# PCB_RGBlimp-Q.net
KiCad netlist of a schematic drawn in Altium Designer
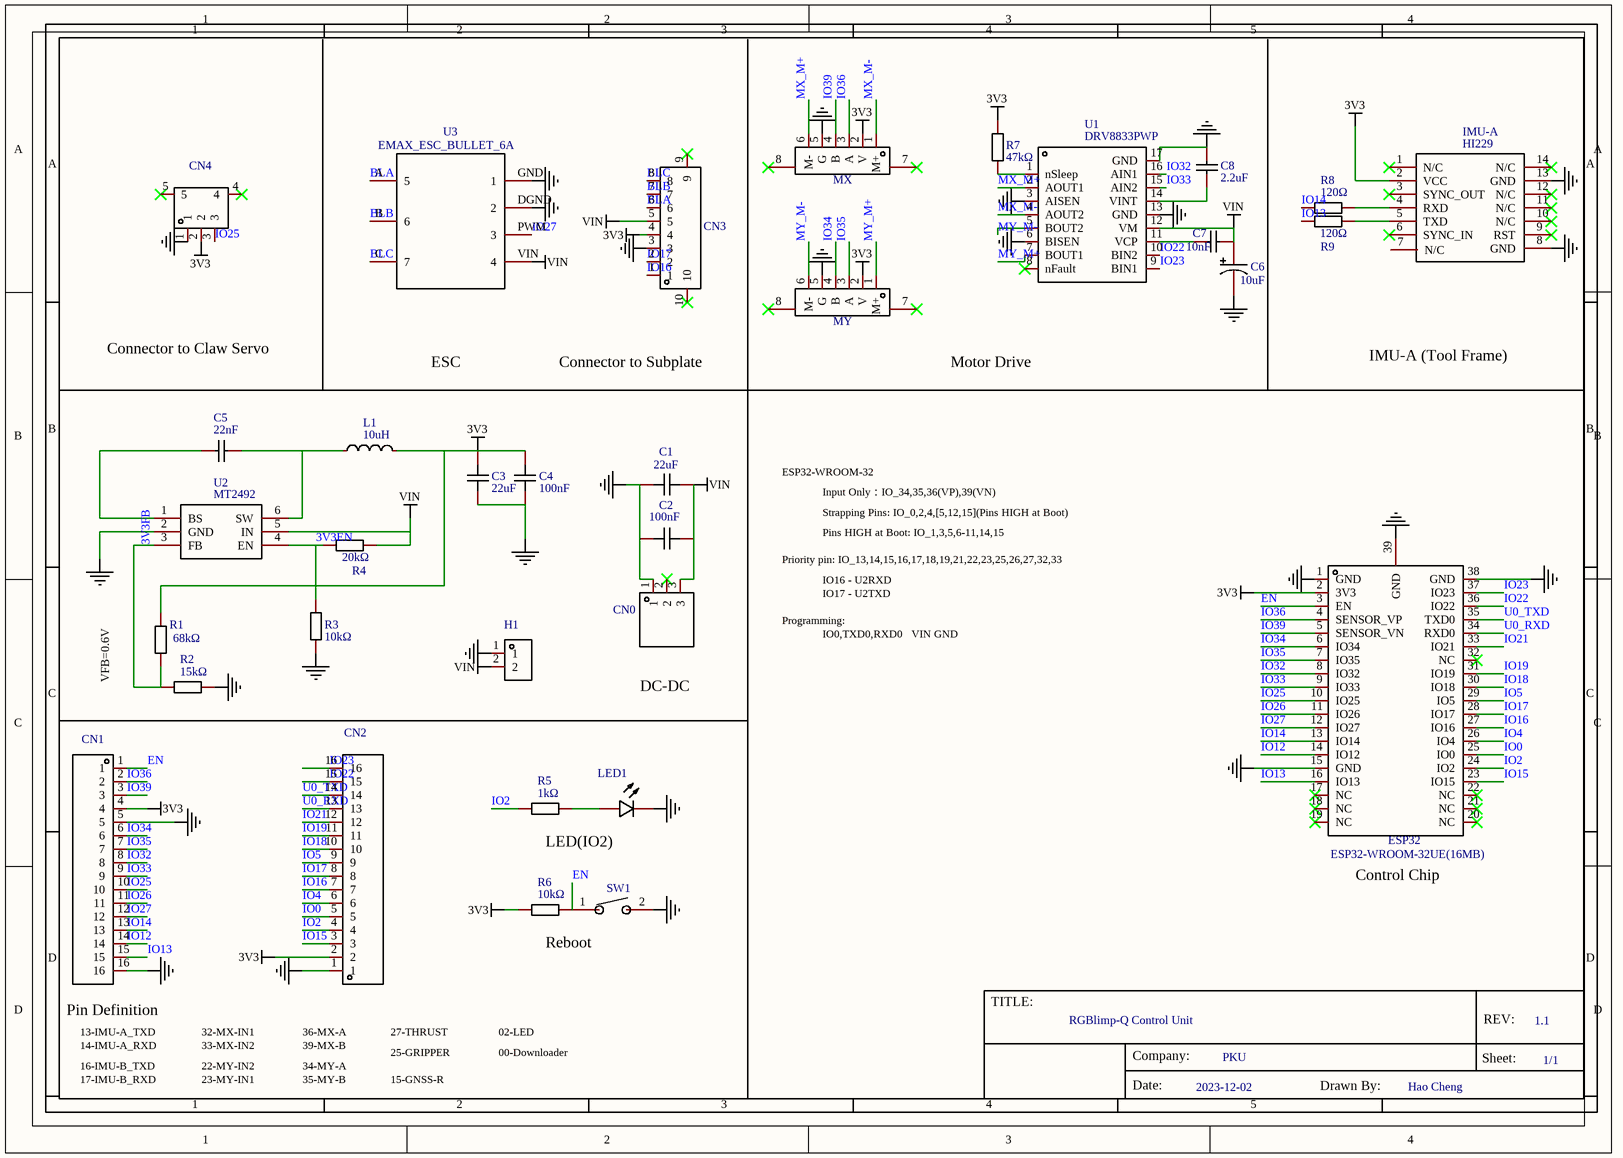
[diagram p0: PCB_RGBlimp-Q.schdoc]

(export (version "E")
  (design (tool "Eeschema 10.0.6"))
  (components
    (comp (ref "C1")
      (value "22uF")
      (fields
        (field (name "NAME") "22uF")
        (field (name "MANUFACTURER") "SAMSUNG(三星)")
        (field (name "MANUFACTURER PART") "CL10A226MQ8NRNC")
      )
      (libsource (lib "altium-import") (part "root_0_22uF_"))
    )
    (comp (ref "C2")
      (value "100nF")
      (fields
        (field (name "NAME") "100nF")
        (field (name "MANUFACTURER") "YAGEO(国巨)")
        (field (name "MANUFACTURER PART") "CC0603KRX7R9BB104")
      )
      (libsource (lib "altium-import") (part "root_0_100nF_"))
    )
    (comp (ref "C3")
      (value "22uF")
      (fields
        (field (name "NAME") "22uF")
        (field (name "MANUFACTURER") "SAMSUNG(三星)")
        (field (name "MANUFACTURER PART") "CL10A226MQ8NRNC")
      )
      (libsource (lib "altium-import") (part "root_3_22uF_"))
    )
    (comp (ref "C4")
      (value "100nF")
      (fields
        (field (name "NAME") "100nF")
        (field (name "MANUFACTURER") "YAGEO(国巨)")
        (field (name "MANUFACTURER PART") "CC0603KRX7R9BB104")
      )
      (libsource (lib "altium-import") (part "root_3_100nF_"))
    )
    (comp (ref "C5")
      (value "22nF")
      (fields
        (field (name "NAME") "22nF")
        (field (name "MANUFACTURER") "FH(风华)")
        (field (name "MANUFACTURER PART") "0603B223K500NT")
      )
      (libsource (lib "altium-import") (part "root_0_22nF_"))
    )
    (comp (ref "C6")
      (value "10uF")
      (fields
        (field (name "NAME") "10uF")
        (field (name "MANUFACTURER") "TORCH(火炬)")
        (field (name "MANUFACTURER PART") "CA45-A-16V-10μF-K")
      )
      (libsource (lib "altium-import") (part "root_3_10uF_"))
    )
    (comp (ref "C7")
      (value "10nF")
      (fields
        (field (name "NAME") "10nF")
        (field (name "MANUFACTURER PART") "GRM188R71H103KA01D")
        (field (name "MANUFACTURER") "muRata(村田)")
      )
      (libsource (lib "altium-import") (part "root_0_10nF_"))
    )
    (comp (ref "C8")
      (value "2.2uF")
      (fields
        (field (name "NAME") "2.2uF")
        (field (name "MANUFACTURER PART") "CL10A225KO8NNNC")
        (field (name "MANUFACTURER") "SAMSUNG(三星)")
      )
      (libsource (lib "altium-import") (part "root_3_2.2uF_"))
    )
    (comp (ref "CN0")
      (value "S3B-XH-A (LF)(SN)")
      (fields (field (name "MANUFACTURER") "JST") (field (name "MANUFACTURER PART") "S3B-XH-A(LF)(SN)"))
      (libsource (lib "altium-import") (part "root_3_S3B-XH-A (LF)(SN)_"))
    )
    (comp (ref "CN1")
      (value "A2005WV-16P")
      (fields (field (name "MANUFACTURER") "Changjiang Connectors"))
      (libsource (lib "altium-import") (part "root_0_A2005WV-16P_"))
    )
    (comp (ref "CN2")
      (value "A2005WV-16P")
      (fields (field (name "MANUFACTURER") "Changjiang Connectors"))
      (libsource (lib "") (part "root_0_A2005WV-16P__1"))
    )
    (comp (ref "CN3")
      (value "AFC12-S08CCC-00")
      (fields (field (name "MANUFACTURER") "JS(钜硕电子)"))
      (libsource (lib "altium-import") (part "root_0_AFC12-S08CCC-00_"))
    )
    (comp (ref "CN4")
      (value "AFC12-S03CCC-00")
      (fields (field (name "MANUFACTURER") "JS(钜硕电子)"))
      (libsource (lib "altium-import") (part "root_1_AFC12-S03CCC-00_"))
    )
    (comp (ref "ESP32")
      (value "ESP32-WROOM-32UE(16MB)")
      (fields
        (field (name "NAME") "ESP32-WROOM-32UE(16MB)")
        (field (name "MANUFACTURER") "ESPRESSIF(乐鑫)")
        (field (name "MANUFACTURER PART") "ESP32-WROOM-32UE-N16")
      )
      (libsource (lib "altium-import") (part "root_0_ESP32-WROOM-32UE(16MB)_"))
    )
    (comp (ref "H1")
      (value "A2005WV-2P_C2879963")
      (fields (field (name "MANUFACTURER") "CJT(长江连接器)") (field (name "MANUFACTURER PART") "A2005WV-2P"))
      (libsource (lib "altium-import") (part "root_0_A2005WV-2P_C2879963_"))
    )
    (comp (ref "IMU-A")
      (value "HI229")
      (fields (field (name "NAME") "HI229"))
      (libsource (lib "altium-import") (part "root_0_HI229_"))
    )
    (comp (ref "L1")
      (value "10uH")
      (fields
        (field (name "NAME") "10uH")
        (field (name "MANUFACTURER") "Sunlord")
        (field (name "MANUFACTURER PART") "SWPA6045S100MT")
      )
      (libsource (lib "altium-import") (part "root_0_10uH_"))
    )
    (comp (ref "LED1")
      (value "FC-DA1608BK-470H10")
      (fields (field (name "MANUFACTURER") "国星光电") (field (name "MANUFACTURER PART") "NCD0603B1"))
      (libsource (lib "altium-import") (part "root_0_FC-DA1608BK-470H10_"))
    )
    (comp (ref "MX")
      (value "KH-FG0.5-H2.0-6PIN")
      (fields (field (name "MANUFACTURER") "Shenzhen Kinghelm Elec"))
      (libsource (lib "altium-import") (part "root_3_KH-FG0.5-H2.0-6PIN_"))
    )
    (comp (ref "MY")
      (value "KH-FG0.5-H2.0-6PIN")
      (fields (field (name "MANUFACTURER") "Shenzhen Kinghelm Elec"))
      (libsource (lib "altium-import") (part "root_3_KH-FG0.5-H2.0-6PIN_"))
    )
    (comp (ref "R1")
      (value "68kΩ")
      (fields
        (field (name "NAME") "68kΩ")
        (field (name "MANUFACTURER") "UNI-ROYAL(厚声)")
        (field (name "MANUFACTURER PART") "0603WAF6802T5E")
      )
      (libsource (lib "altium-import") (part "root_3_68kΩ_"))
    )
    (comp (ref "R2")
      (value "15kΩ")
      (fields
        (field (name "NAME") "15kΩ")
        (field (name "MANUFACTURER") "UNI-ROYAL(厚声)")
        (field (name "MANUFACTURER PART") "0603WAF1502T5E")
      )
      (libsource (lib "altium-import") (part "root_0_15kΩ_"))
    )
    (comp (ref "R3")
      (value "10kΩ")
      (fields
        (field (name "NAME") "10kΩ")
        (field (name "MANUFACTURER") "UNI-ROYAL(厚声)")
        (field (name "MANUFACTURER PART") "0603WAF1002T5E")
      )
      (libsource (lib "altium-import") (part "root_3_10kΩ_"))
    )
    (comp (ref "R4")
      (value "20kΩ")
      (fields
        (field (name "NAME") "20kΩ")
        (field (name "MANUFACTURER") "UNI-ROYAL(厚声)")
        (field (name "MANUFACTURER PART") "0603WAF2002T5E")
      )
      (libsource (lib "altium-import") (part "root_0_20kΩ_"))
    )
    (comp (ref "R5")
      (value "1kΩ")
      (fields
        (field (name "NAME") "1kΩ")
        (field (name "MANUFACTURER") "UNI-ROYAL(厚声)")
        (field (name "MANUFACTURER PART") "0603WAF1001T5E")
      )
      (libsource (lib "altium-import") (part "root_0_1kΩ_"))
    )
    (comp (ref "R6")
      (value "10kΩ")
      (fields
        (field (name "NAME") "10kΩ")
        (field (name "MANUFACTURER") "UNI-ROYAL(厚声)")
        (field (name "MANUFACTURER PART") "0603WAF1002T5E")
      )
      (libsource (lib "altium-import") (part "root_0_10kΩ_"))
    )
    (comp (ref "R7")
      (value "47kΩ")
      (fields
        (field (name "NAME") "47kΩ")
        (field (name "MANUFACTURER") "UNI-ROYAL(厚声)")
        (field (name "MANUFACTURER PART") "0603WAF4702T5E")
      )
      (libsource (lib "altium-import") (part "root_3_47kΩ_"))
    )
    (comp (ref "R8")
      (value "120Ω")
      (fields
        (field (name "NAME") "120Ω")
        (field (name "MANUFACTURER") "UNI-ROYAL(厚声)")
        (field (name "MANUFACTURER PART") "0603WAF1200T5E")
      )
      (libsource (lib "altium-import") (part "root_0_120Ω_"))
    )
    (comp (ref "R9")
      (value "120Ω")
      (fields
        (field (name "NAME") "120Ω")
        (field (name "MANUFACTURER") "UNI-ROYAL(厚声)")
        (field (name "MANUFACTURER PART") "0603WAF1200T5E")
      )
      (libsource (lib "altium-import") (part "root_0_120Ω_"))
    )
    (comp (ref "SW1")
      (value "TSA343G00D-250J2")
      (fields (field (name "MANUFACTURER") "BRIGHT"))
      (libsource (lib "altium-import") (part "root_0_TSA343G00D-250J2_"))
    )
    (comp (ref "U1")
      (value "DRV8833PWP")
      (fields
        (field (name "NAME") "DRV8833PWP")
        (field (name "MANUFACTURER") "TI(德州仪器)")
        (field (name "MANUFACTURER PART") "DRV8833PWPR")
      )
      (libsource (lib "altium-import") (part "root_0_DRV8833PWP_"))
    )
    (comp (ref "U2")
      (value "MT2492")
      (fields (field (name "NAME") "MT2492") (field (name "MANUFACTURER") "AEROSEMI"))
      (libsource (lib "altium-import") (part "root_0_MT2492_"))
    )
    (comp (ref "U3")
      (value "EMAX_ESC_BULLET_6A")
      (fields (field (name "NAME") "EMAX_ESC_BULLET_6A"))
      (libsource (lib "altium-import") (part "root_0_EMAX_ESC_BULLET_6A_"))
    )
  )
  (nets
    (net (code "1") (name "/3V3EN") (class "Default")
      (node (ref "R3") (pin "1") (pinfunction "1_1") (pintype "passive"))
      (node (ref "R4") (pin "1") (pinfunction "1_1") (pintype "passive"))
      (node (ref "U2") (pin "4") (pinfunction "EN_4") (pintype "passive"))
    )
    (net (code "2") (name "/3V3FB") (class "Default")
      (node (ref "R1") (pin "2") (pinfunction "2_2") (pintype "passive"))
      (node (ref "R2") (pin "1") (pinfunction "1_1") (pintype "passive"))
      (node (ref "U2") (pin "3") (pinfunction "FB_3") (pintype "passive"))
    )
    (net (code "3") (name "/BLA") (class "Default")
      (node (ref "CN3") (pin "6") (pinfunction "6_6") (pintype "passive"))
      (node (ref "U3") (pin "A") (pinfunction "5_A") (pintype "passive"))
    )
    (net (code "4") (name "/BLB") (class "Default")
      (node (ref "CN3") (pin "7") (pinfunction "7_7") (pintype "passive"))
      (node (ref "U3") (pin "B") (pinfunction "6_B") (pintype "passive"))
    )
    (net (code "5") (name "/BLC") (class "Default")
      (node (ref "CN3") (pin "8") (pinfunction "8_8") (pintype "passive"))
      (node (ref "U3") (pin "C") (pinfunction "7_C") (pintype "passive"))
    )
    (net (code "6") (name "/EN") (class "Default")
      (node (ref "CN1") (pin "1") (pinfunction "1_1") (pintype "passive"))
      (node (ref "ESP32") (pin "3") (pinfunction "EN_3") (pintype "passive"))
      (node (ref "R6") (pin "2") (pinfunction "2_2") (pintype "passive"))
      (node (ref "SW1") (pin "1") (pinfunction "1_1") (pintype "passive"))
    )
    (net (code "7") (name "/IO0") (class "Default")
      (node (ref "CN2") (pin "5") (pinfunction "5_5") (pintype "passive"))
      (node (ref "ESP32") (pin "25") (pinfunction "IO0_25") (pintype "passive"))
    )
    (net (code "8") (name "/IO2") (class "Default")
      (node (ref "CN2") (pin "4") (pinfunction "4_4") (pintype "passive"))
      (node (ref "ESP32") (pin "24") (pinfunction "IO2_24") (pintype "passive"))
      (node (ref "R5") (pin "1") (pinfunction "1_1") (pintype "passive"))
    )
    (net (code "9") (name "/IO4") (class "Default")
      (node (ref "CN2") (pin "6") (pinfunction "6_6") (pintype "passive"))
      (node (ref "ESP32") (pin "26") (pinfunction "IO4_26") (pintype "passive"))
    )
    (net (code "10") (name "/IO5") (class "Default")
      (node (ref "CN2") (pin "9") (pinfunction "9_9") (pintype "passive"))
      (node (ref "ESP32") (pin "29") (pinfunction "IO5_29") (pintype "passive"))
    )
    (net (code "11") (name "/IO12") (class "Default")
      (node (ref "CN1") (pin "14") (pinfunction "14_14") (pintype "passive"))
      (node (ref "ESP32") (pin "14") (pinfunction "IO12_14") (pintype "passive"))
    )
    (net (code "12") (name "/IO13") (class "Default")
      (node (ref "CN1") (pin "15") (pinfunction "15_15") (pintype "passive"))
      (node (ref "ESP32") (pin "16") (pinfunction "IO13_16") (pintype "passive"))
      (node (ref "R9") (pin "1") (pinfunction "1_1") (pintype "passive"))
    )
    (net (code "13") (name "/IO14") (class "Default")
      (node (ref "CN1") (pin "13") (pinfunction "13_13") (pintype "passive"))
      (node (ref "ESP32") (pin "13") (pinfunction "IO14_13") (pintype "passive"))
      (node (ref "R8") (pin "1") (pinfunction "1_1") (pintype "passive"))
    )
    (net (code "14") (name "/IO15") (class "Default")
      (node (ref "CN2") (pin "3") (pinfunction "3_3") (pintype "passive"))
      (node (ref "ESP32") (pin "23") (pinfunction "IO15_23") (pintype "passive"))
    )
    (net (code "15") (name "/IO16") (class "Default")
      (node (ref "CN2") (pin "7") (pinfunction "7_7") (pintype "passive"))
      (node (ref "CN3") (pin "1") (pinfunction "1_1") (pintype "passive"))
      (node (ref "ESP32") (pin "27") (pinfunction "IO16_27") (pintype "passive"))
    )
    (net (code "16") (name "/IO17") (class "Default")
      (node (ref "CN2") (pin "8") (pinfunction "8_8") (pintype "passive"))
      (node (ref "CN3") (pin "2") (pinfunction "2_2") (pintype "passive"))
      (node (ref "ESP32") (pin "28") (pinfunction "IO17_28") (pintype "passive"))
    )
    (net (code "17") (name "/IO18") (class "Default")
      (node (ref "CN2") (pin "10") (pinfunction "10_10") (pintype "passive"))
      (node (ref "ESP32") (pin "30") (pinfunction "IO18_30") (pintype "passive"))
    )
    (net (code "18") (name "/IO19") (class "Default")
      (node (ref "CN2") (pin "11") (pinfunction "11_11") (pintype "passive"))
      (node (ref "ESP32") (pin "31") (pinfunction "IO19_31") (pintype "passive"))
    )
    (net (code "19") (name "/IO21") (class "Default")
      (node (ref "CN2") (pin "12") (pinfunction "12_12") (pintype "passive"))
      (node (ref "ESP32") (pin "33") (pinfunction "IO21_33") (pintype "passive"))
    )
    (net (code "20") (name "/IO22") (class "Default")
      (node (ref "CN2") (pin "15") (pinfunction "15_15") (pintype "passive"))
      (node (ref "ESP32") (pin "36") (pinfunction "IO22_36") (pintype "passive"))
      (node (ref "U1") (pin "10") (pinfunction "BIN2_10") (pintype "passive"))
    )
    (net (code "21") (name "/IO23") (class "Default")
      (node (ref "CN2") (pin "16") (pinfunction "16_16") (pintype "passive"))
      (node (ref "ESP32") (pin "37") (pinfunction "IO23_37") (pintype "passive"))
      (node (ref "U1") (pin "9") (pinfunction "BIN1_9") (pintype "passive"))
    )
    (net (code "22") (name "/IO25") (class "Default")
      (node (ref "CN1") (pin "10") (pinfunction "10_10") (pintype "passive"))
      (node (ref "CN4") (pin "3") (pinfunction "3_3") (pintype "passive"))
      (node (ref "ESP32") (pin "10") (pinfunction "IO25_10") (pintype "passive"))
    )
    (net (code "23") (name "/IO26") (class "Default")
      (node (ref "CN1") (pin "11") (pinfunction "11_11") (pintype "passive"))
      (node (ref "ESP32") (pin "11") (pinfunction "IO26_11") (pintype "passive"))
    )
    (net (code "24") (name "/IO27") (class "Default")
      (node (ref "CN1") (pin "12") (pinfunction "12_12") (pintype "passive"))
      (node (ref "ESP32") (pin "12") (pinfunction "IO27_12") (pintype "passive"))
      (node (ref "U3") (pin "PWM") (pinfunction "3_PWM") (pintype "passive"))
    )
    (net (code "25") (name "/IO32") (class "Default")
      (node (ref "CN1") (pin "8") (pinfunction "8_8") (pintype "passive"))
      (node (ref "ESP32") (pin "8") (pinfunction "IO32_8") (pintype "passive"))
      (node (ref "U1") (pin "16") (pinfunction "AIN1_16") (pintype "passive"))
    )
    (net (code "26") (name "/IO33") (class "Default")
      (node (ref "CN1") (pin "9") (pinfunction "9_9") (pintype "passive"))
      (node (ref "ESP32") (pin "9") (pinfunction "IO33_9") (pintype "passive"))
      (node (ref "U1") (pin "15") (pinfunction "AIN2_15") (pintype "passive"))
    )
    (net (code "27") (name "/IO34") (class "Default")
      (node (ref "CN1") (pin "6") (pinfunction "6_6") (pintype "passive"))
      (node (ref "ESP32") (pin "6") (pinfunction "IO34_6") (pintype "passive"))
      (node (ref "MY") (pin "4") (pinfunction "B_4") (pintype "passive"))
    )
    (net (code "28") (name "/IO35") (class "Default")
      (node (ref "CN1") (pin "7") (pinfunction "7_7") (pintype "passive"))
      (node (ref "ESP32") (pin "7") (pinfunction "IO35_7") (pintype "passive"))
      (node (ref "MY") (pin "3") (pinfunction "A_3") (pintype "passive"))
    )
    (net (code "29") (name "/IO36") (class "Default")
      (node (ref "CN1") (pin "2") (pinfunction "2_2") (pintype "passive"))
      (node (ref "ESP32") (pin "4") (pinfunction "SENSOR_VP_4") (pintype "passive"))
      (node (ref "MX") (pin "3") (pinfunction "A_3") (pintype "passive"))
    )
    (net (code "30") (name "/IO39") (class "Default")
      (node (ref "CN1") (pin "3") (pinfunction "3_3") (pintype "passive"))
      (node (ref "ESP32") (pin "5") (pinfunction "SENSOR_VN_5") (pintype "passive"))
      (node (ref "MX") (pin "4") (pinfunction "B_4") (pintype "passive"))
    )
    (net (code "31") (name "/MX_M+") (class "Default")
      (node (ref "MX") (pin "6") (pinfunction "M-_6") (pintype "passive"))
      (node (ref "U1") (pin "2") (pinfunction "AOUT1_2") (pintype "passive"))
    )
    (net (code "32") (name "/MX_M-") (class "Default")
      (node (ref "MX") (pin "1") (pinfunction "M+_1") (pintype "passive"))
      (node (ref "U1") (pin "4") (pinfunction "AOUT2_4") (pintype "passive"))
    )
    (net (code "33") (name "/MY_M+") (class "Default")
      (node (ref "MY") (pin "1") (pinfunction "M+_1") (pintype "passive"))
      (node (ref "U1") (pin "7") (pinfunction "BOUT1_7") (pintype "passive"))
    )
    (net (code "34") (name "/MY_M-") (class "Default")
      (node (ref "MY") (pin "6") (pinfunction "M-_6") (pintype "passive"))
      (node (ref "U1") (pin "5") (pinfunction "BOUT2_5") (pintype "passive"))
    )
    (net (code "35") (name "/U0_RXD") (class "Default")
      (node (ref "CN2") (pin "13") (pinfunction "13_13") (pintype "passive"))
      (node (ref "ESP32") (pin "34") (pinfunction "RXD0_34") (pintype "passive"))
    )
    (net (code "36") (name "/U0_TXD") (class "Default")
      (node (ref "CN2") (pin "14") (pinfunction "14_14") (pintype "passive"))
      (node (ref "ESP32") (pin "35") (pinfunction "TXD0_35") (pintype "passive"))
    )
    (net (code "37") (name "3V3") (class "Default")
      (node (ref "C3") (pin "1") (pinfunction "1_1") (pintype "passive"))
      (node (ref "C4") (pin "1") (pinfunction "1_1") (pintype "passive"))
      (node (ref "CN1") (pin "4") (pinfunction "4_4") (pintype "passive"))
      (node (ref "CN2") (pin "2") (pinfunction "2_2") (pintype "passive"))
      (node (ref "CN3") (pin "4") (pinfunction "4_4") (pintype "passive"))
      (node (ref "CN4") (pin "2") (pinfunction "2_2") (pintype "passive"))
      (node (ref "ESP32") (pin "2") (pinfunction "3V3_2") (pintype "passive"))
      (node (ref "IMU-A") (pin "2") (pinfunction "VCC_2") (pintype "passive"))
      (node (ref "L1") (pin "2") (pinfunction "2_2") (pintype "passive"))
      (node (ref "MX") (pin "2") (pinfunction "V_2") (pintype "passive"))
      (node (ref "MY") (pin "2") (pinfunction "V_2") (pintype "passive"))
      (node (ref "R1") (pin "1") (pinfunction "1_1") (pintype "passive"))
      (node (ref "R6") (pin "1") (pinfunction "1_1") (pintype "passive"))
      (node (ref "R7") (pin "1") (pinfunction "1_1") (pintype "passive"))
    )
    (net (code "38") (name "GND") (class "Default")
      (node (ref "C1") (pin "1") (pinfunction "1_1") (pintype "passive"))
      (node (ref "C2") (pin "1") (pinfunction "1_1") (pintype "passive"))
      (node (ref "C3") (pin "2") (pinfunction "2_2") (pintype "passive"))
      (node (ref "C4") (pin "2") (pinfunction "2_2") (pintype "passive"))
      (node (ref "C6") (pin "2") (pinfunction "2_2") (pintype "passive"))
      (node (ref "C8") (pin "1") (pinfunction "1_1") (pintype "passive"))
      (node (ref "CN0") (pin "1") (pinfunction "1_1") (pintype "passive"))
      (node (ref "CN1") (pin "16") (pinfunction "16_16") (pintype "passive"))
      (node (ref "CN1") (pin "5") (pinfunction "5_5") (pintype "passive"))
      (node (ref "CN2") (pin "1") (pinfunction "1_1") (pintype "passive"))
      (node (ref "CN3") (pin "3") (pinfunction "3_3") (pintype "passive"))
      (node (ref "CN4") (pin "1") (pinfunction "1_1") (pintype "passive"))
      (node (ref "ESP32") (pin "1") (pinfunction "GND_1") (pintype "passive"))
      (node (ref "ESP32") (pin "15") (pinfunction "GND_15") (pintype "passive"))
      (node (ref "ESP32") (pin "38") (pinfunction "GND_38") (pintype "passive"))
      (node (ref "ESP32") (pin "39") (pinfunction "GND_39") (pintype "passive"))
      (node (ref "H1") (pin "1") (pinfunction "1_1") (pintype "passive"))
      (node (ref "IMU-A") (pin "13") (pinfunction "GND_13") (pintype "passive"))
      (node (ref "IMU-A") (pin "8") (pinfunction "GND_8") (pintype "passive"))
      (node (ref "LED1") (pin "1") (pinfunction "-_1") (pintype "passive"))
      (node (ref "MX") (pin "5") (pinfunction "G_5") (pintype "passive"))
      (node (ref "MY") (pin "5") (pinfunction "G_5") (pintype "passive"))
      (node (ref "R2") (pin "2") (pinfunction "2_2") (pintype "passive"))
      (node (ref "R3") (pin "2") (pinfunction "2_2") (pintype "passive"))
      (node (ref "SW1") (pin "2") (pinfunction "2_2") (pintype "passive"))
      (node (ref "U1") (pin "13") (pinfunction "GND_13") (pintype "passive"))
      (node (ref "U1") (pin "17") (pinfunction "GND_17") (pintype "passive"))
      (node (ref "U1") (pin "3") (pinfunction "AISEN_3") (pintype "passive"))
      (node (ref "U1") (pin "6") (pinfunction "BISEN_6") (pintype "passive"))
      (node (ref "U2") (pin "2") (pinfunction "GND_2") (pintype "passive"))
      (node (ref "U3") (pin "DGND") (pinfunction "2_DGND") (pintype "passive"))
      (node (ref "U3") (pin "GND") (pinfunction "1_GND") (pintype "passive"))
    )
    (net (code "39") (name "Net-(IMU-A-RXD)") (class "Default")
      (node (ref "IMU-A") (pin "4") (pinfunction "RXD_4") (pintype "passive"))
      (node (ref "R8") (pin "2") (pinfunction "2_2") (pintype "passive"))
    )
    (net (code "40") (name "Net-(IMU-A-TXD)") (class "Default")
      (node (ref "IMU-A") (pin "5") (pinfunction "TXD_5") (pintype "passive"))
      (node (ref "R9") (pin "2") (pinfunction "2_2") (pintype "passive"))
    )
    (net (code "41") (name "Net-(LED1-+)") (class "Default")
      (node (ref "LED1") (pin "2") (pinfunction "+_2") (pintype "passive"))
      (node (ref "R5") (pin "2") (pinfunction "2_2") (pintype "passive"))
    )
    (net (code "42") (name "Net-(U1-VCP)") (class "Default")
      (node (ref "C7") (pin "1") (pinfunction "1_1") (pintype "passive"))
      (node (ref "U1") (pin "11") (pinfunction "VCP_11") (pintype "passive"))
    )
    (net (code "43") (name "Net-(U1-VINT)") (class "Default")
      (node (ref "C8") (pin "2") (pinfunction "2_2") (pintype "passive"))
      (node (ref "U1") (pin "14") (pinfunction "VINT_14") (pintype "passive"))
    )
    (net (code "44") (name "Net-(U1-nSleep)") (class "Default")
      (node (ref "R7") (pin "2") (pinfunction "2_2") (pintype "passive"))
      (node (ref "U1") (pin "1") (pinfunction "nSleep_1") (pintype "passive"))
    )
    (net (code "45") (name "Net-(U2-BS)") (class "Default")
      (node (ref "C5") (pin "1") (pinfunction "1_1") (pintype "passive"))
      (node (ref "U2") (pin "1") (pinfunction "BS_1") (pintype "passive"))
    )
    (net (code "46") (name "Net-(U2-SW)") (class "Default")
      (node (ref "C5") (pin "2") (pinfunction "2_2") (pintype "passive"))
      (node (ref "L1") (pin "1") (pinfunction "1_1") (pintype "passive"))
      (node (ref "U2") (pin "6") (pinfunction "SW_6") (pintype "passive"))
    )
    (net (code "47") (name "VIN") (class "Default")
      (node (ref "C1") (pin "2") (pinfunction "2_2") (pintype "passive"))
      (node (ref "C2") (pin "2") (pinfunction "2_2") (pintype "passive"))
      (node (ref "C6") (pin "1") (pinfunction "1_1") (pintype "passive"))
      (node (ref "C7") (pin "2") (pinfunction "2_2") (pintype "passive"))
      (node (ref "CN0") (pin "3") (pinfunction "3_3") (pintype "passive"))
      (node (ref "CN3") (pin "5") (pinfunction "5_5") (pintype "passive"))
      (node (ref "H1") (pin "2") (pinfunction "2_2") (pintype "passive"))
      (node (ref "R4") (pin "2") (pinfunction "2_2") (pintype "passive"))
      (node (ref "U1") (pin "12") (pinfunction "VM_12") (pintype "passive"))
      (node (ref "U2") (pin "5") (pinfunction "IN_5") (pintype "passive"))
      (node (ref "U3") (pin "VIN") (pinfunction "4_VIN") (pintype "passive"))
    )
    (net (code "48") (name "unconnected-(CN0-Pad2)") (class "Default")
      (node (ref "CN0") (pin "2") (pinfunction "2_2") (pintype "passive+no_connect"))
    )
    (net (code "49") (name "unconnected-(CN3-Pad9)") (class "Default")
      (node (ref "CN3") (pin "9") (pinfunction "9_9") (pintype "passive+no_connect"))
    )
    (net (code "50") (name "unconnected-(CN3-Pad10)") (class "Default")
      (node (ref "CN3") (pin "10") (pinfunction "10_10") (pintype "passive+no_connect"))
    )
    (net (code "51") (name "unconnected-(CN4-Pad4)") (class "Default")
      (node (ref "CN4") (pin "4") (pinfunction "4_4") (pintype "passive+no_connect"))
    )
    (net (code "52") (name "unconnected-(CN4-Pad5)") (class "Default")
      (node (ref "CN4") (pin "5") (pinfunction "5_5") (pintype "passive+no_connect"))
    )
    (net (code "53") (name "unconnected-(ESP32-NC-Pad17)") (class "Default")
      (node (ref "ESP32") (pin "17") (pinfunction "NC_17") (pintype "passive+no_connect"))
    )
    (net (code "54") (name "unconnected-(ESP32-NC-Pad18)") (class "Default")
      (node (ref "ESP32") (pin "18") (pinfunction "NC_18") (pintype "passive+no_connect"))
    )
    (net (code "55") (name "unconnected-(ESP32-NC-Pad19)") (class "Default")
      (node (ref "ESP32") (pin "19") (pinfunction "NC_19") (pintype "passive+no_connect"))
    )
    (net (code "56") (name "unconnected-(ESP32-NC-Pad20)") (class "Default")
      (node (ref "ESP32") (pin "20") (pinfunction "NC_20") (pintype "passive+no_connect"))
    )
    (net (code "57") (name "unconnected-(ESP32-NC-Pad21)") (class "Default")
      (node (ref "ESP32") (pin "21") (pinfunction "NC_21") (pintype "passive+no_connect"))
    )
    (net (code "58") (name "unconnected-(ESP32-NC-Pad22)") (class "Default")
      (node (ref "ESP32") (pin "22") (pinfunction "NC_22") (pintype "passive+no_connect"))
    )
    (net (code "59") (name "unconnected-(ESP32-NC-Pad32)") (class "Default")
      (node (ref "ESP32") (pin "32") (pinfunction "NC_32") (pintype "passive+no_connect"))
    )
    (net (code "60") (name "unconnected-(IMU-A-N{slash}C-Pad1)") (class "Default")
      (node (ref "IMU-A") (pin "1") (pinfunction "N/C_1") (pintype "passive+no_connect"))
    )
    (net (code "61") (name "unconnected-(IMU-A-N{slash}C-Pad7)") (class "Default")
      (node (ref "IMU-A") (pin "7") (pinfunction "N/C_7") (pintype "passive"))
    )
    (net (code "62") (name "unconnected-(IMU-A-N{slash}C-Pad10)") (class "Default")
      (node (ref "IMU-A") (pin "10") (pinfunction "N/C_10") (pintype "passive+no_connect"))
    )
    (net (code "63") (name "unconnected-(IMU-A-N{slash}C-Pad11)") (class "Default")
      (node (ref "IMU-A") (pin "11") (pinfunction "N/C_11") (pintype "passive+no_connect"))
    )
    (net (code "64") (name "unconnected-(IMU-A-N{slash}C-Pad12)") (class "Default")
      (node (ref "IMU-A") (pin "12") (pinfunction "N/C_12") (pintype "passive+no_connect"))
    )
    (net (code "65") (name "unconnected-(IMU-A-N{slash}C-Pad14)") (class "Default")
      (node (ref "IMU-A") (pin "14") (pinfunction "N/C_14") (pintype "passive+no_connect"))
    )
    (net (code "66") (name "unconnected-(IMU-A-RST-Pad9)") (class "Default")
      (node (ref "IMU-A") (pin "9") (pinfunction "RST_9") (pintype "passive+no_connect"))
    )
    (net (code "67") (name "unconnected-(IMU-A-SYNC_IN-Pad6)") (class "Default")
      (node (ref "IMU-A") (pin "6") (pinfunction "SYNC_IN_6") (pintype "passive+no_connect"))
    )
    (net (code "68") (name "unconnected-(IMU-A-SYNC_OUT-Pad3)") (class "Default")
      (node (ref "IMU-A") (pin "3") (pinfunction "SYNC_OUT_3") (pintype "passive+no_connect"))
    )
    (net (code "69") (name "unconnected-(MX-Pad7)") (class "Default")
      (node (ref "MX") (pin "7") (pintype "passive+no_connect"))
    )
    (net (code "70") (name "unconnected-(MX-Pad8)") (class "Default")
      (node (ref "MX") (pin "8") (pintype "passive+no_connect"))
    )
    (net (code "71") (name "unconnected-(MY-Pad7)") (class "Default")
      (node (ref "MY") (pin "7") (pintype "passive+no_connect"))
    )
    (net (code "72") (name "unconnected-(MY-Pad8)") (class "Default")
      (node (ref "MY") (pin "8") (pintype "passive+no_connect"))
    )
    (net (code "73") (name "unconnected-(U1-nFault-Pad8)") (class "Default")
      (node (ref "U1") (pin "8") (pinfunction "nFault_8") (pintype "passive+no_connect"))
    )
  )
)
